# plugin-sensor.net
KiCad netlist of a schematic drawn in EAGLE
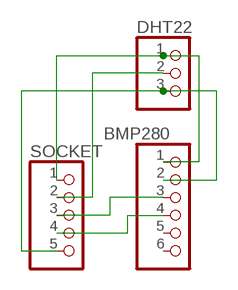
[diagram p0: schematic, sheet 1]

(export (version "E")
  (design (tool "Eeschema 10.0.6"))
  (components
    (comp (ref "BMP280")
      (value "PINHD-1X6/90")
      (footprint "eagle-import:1X06_90")
      (libsource (lib "eagle-import") (part "PINHD-1X6/90"))
    )
    (comp (ref "DHT22")
      (value "PINHD-1X3")
      (footprint "eagle-import:1X03")
      (libsource (lib "eagle-import") (part "PINHD-1X3"))
    )
    (comp (ref "SOCKET")
      (value "PINHD-1X5/90")
      (footprint "eagle-import:1X05_90")
      (libsource (lib "eagle-import") (part "PINHD-1X5/90"))
    )
  )
  (nets
    (net (code "1") (name "Net-(BMP280-Pad1)") (class "Default")
      (node (ref "BMP280") (pin "1") (pinfunction "1_1") (pintype "passive"))
      (node (ref "DHT22") (pin "1") (pinfunction "1_1") (pintype "passive"))
      (node (ref "SOCKET") (pin "1") (pinfunction "1_1") (pintype "passive"))
    )
    (net (code "2") (name "Net-(BMP280-Pad2)") (class "Default")
      (node (ref "BMP280") (pin "2") (pinfunction "2_2") (pintype "passive"))
      (node (ref "DHT22") (pin "3") (pinfunction "3_3") (pintype "passive"))
      (node (ref "SOCKET") (pin "5") (pinfunction "5_5") (pintype "passive"))
    )
    (net (code "3") (name "Net-(BMP280-Pad3)") (class "Default")
      (node (ref "BMP280") (pin "3") (pinfunction "3_3") (pintype "passive"))
      (node (ref "SOCKET") (pin "3") (pinfunction "3_3") (pintype "passive"))
    )
    (net (code "4") (name "Net-(BMP280-Pad4)") (class "Default")
      (node (ref "BMP280") (pin "4") (pinfunction "4_4") (pintype "passive"))
      (node (ref "SOCKET") (pin "4") (pinfunction "4_4") (pintype "passive"))
    )
    (net (code "5") (name "Net-(DHT22-Pad2)") (class "Default")
      (node (ref "DHT22") (pin "2") (pinfunction "2_2") (pintype "passive"))
      (node (ref "SOCKET") (pin "2") (pinfunction "2_2") (pintype "passive"))
    )
    (net (code "6") (name "unconnected-(BMP280-Pad5)") (class "Default")
      (node (ref "BMP280") (pin "5") (pinfunction "5_5") (pintype "passive"))
    )
    (net (code "7") (name "unconnected-(BMP280-Pad6)") (class "Default")
      (node (ref "BMP280") (pin "6") (pinfunction "6_6") (pintype "passive"))
    )
  )
)
